# Adafruit_DragonTail.net
KiCad netlist of a schematic drawn in EAGLE
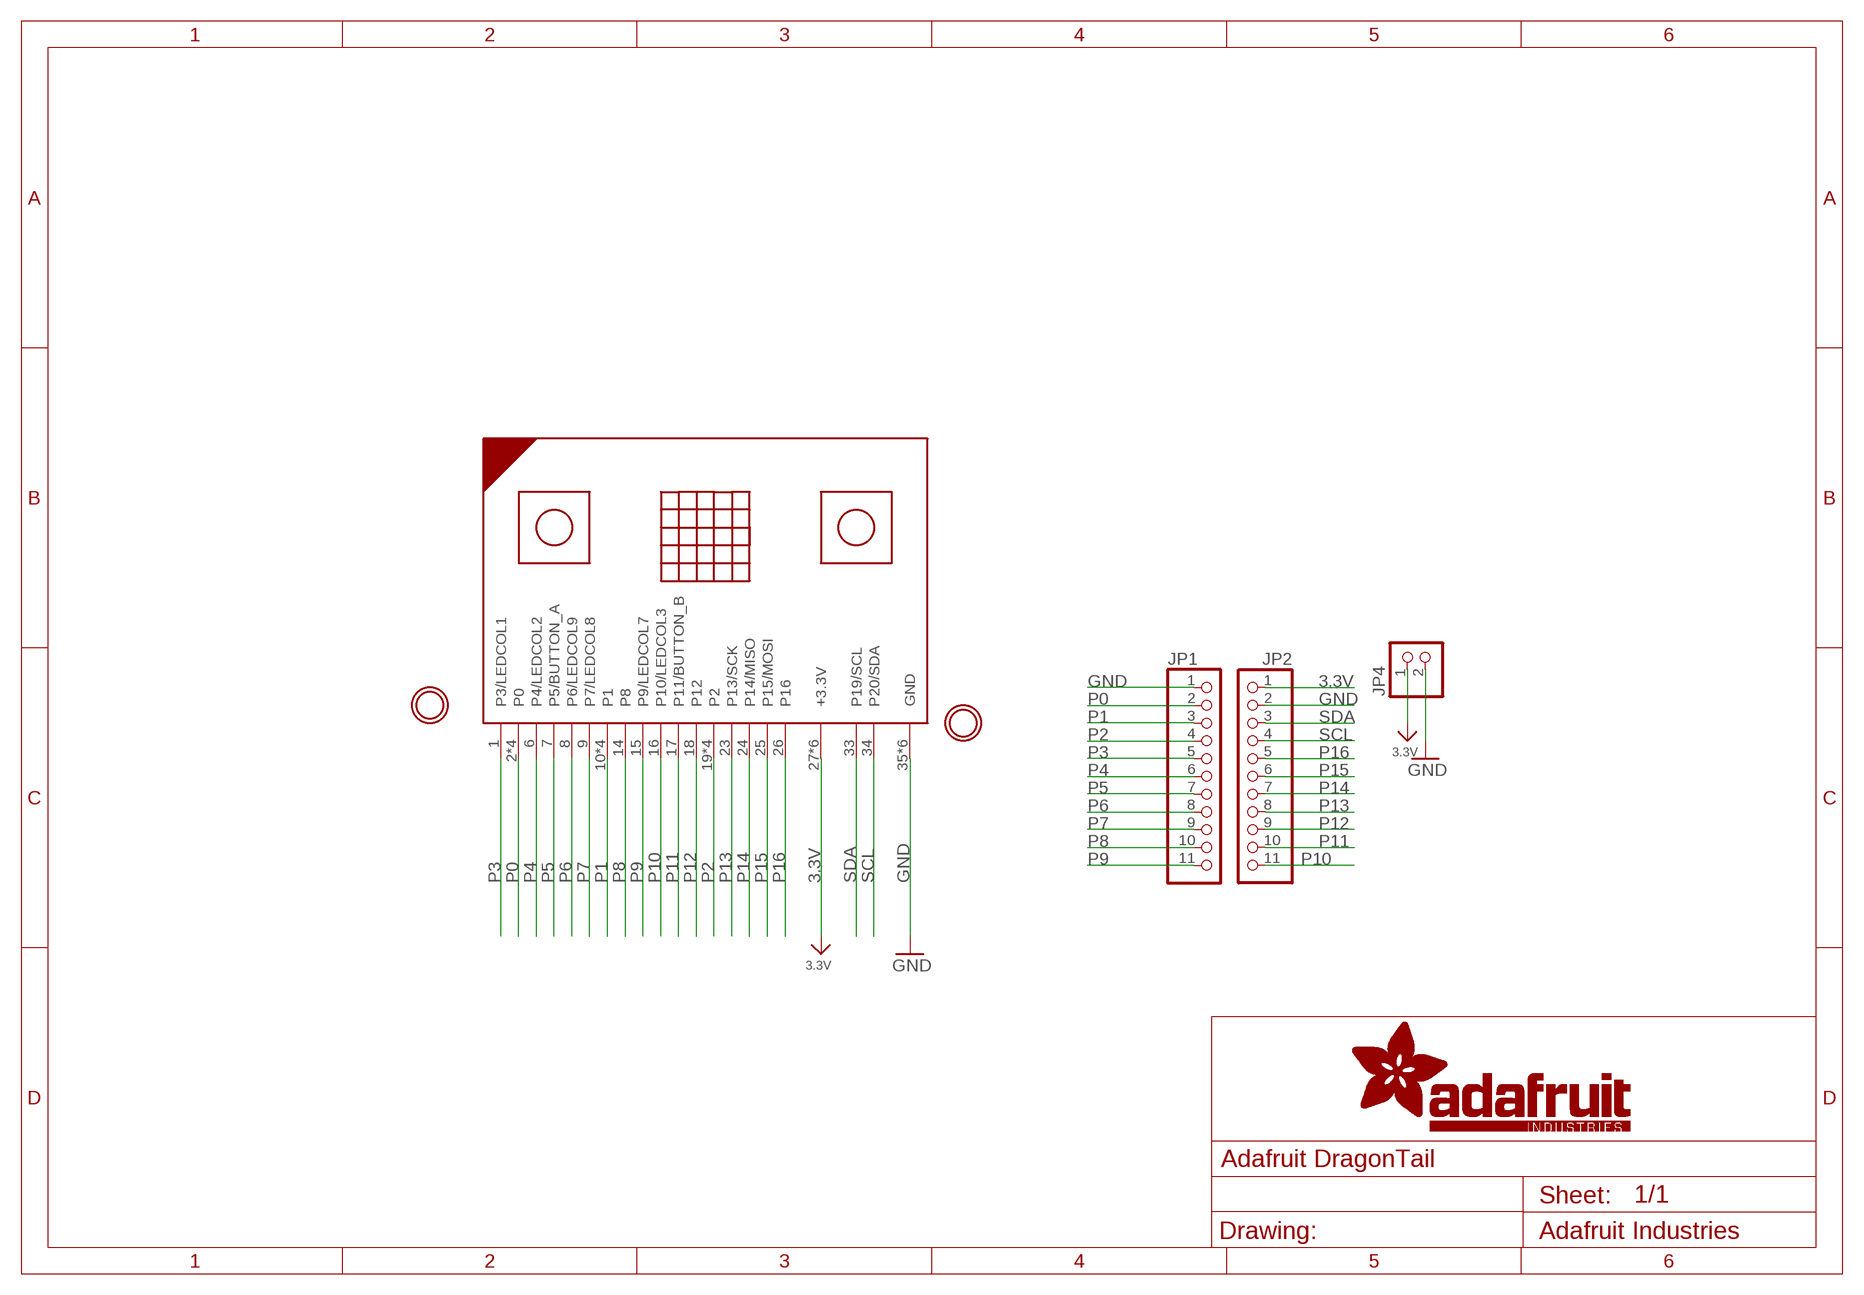
[diagram p0: schematic, sheet 1]

(export (version "E")
  (design (tool "Eeschema 10.0.6"))
  (components
    (comp (ref "JP1")
      (value "HEADER-1X1176MIL")
      (footprint "eagle-import:1X11_ROUND_76")
      (libsource (lib "eagle-import") (part "HEADER-1X1176MIL"))
    )
    (comp (ref "JP2")
      (value "HEADER-1X1176MIL")
      (footprint "eagle-import:1X11_ROUND_76")
      (libsource (lib "eagle-import") (part "HEADER-1X1176MIL"))
    )
    (comp (ref "JP4")
      (value "HEADER-1X2")
      (footprint "eagle-import:1X02_OVAL")
      (libsource (lib "eagle-import") (part "HEADER-1X2"))
    )
    (comp (ref "MB1")
      (value "MICRO:BIT_RA")
      (footprint "eagle-import:2X20_CARDEDGE_RA")
      (libsource (lib "eagle-import") (part "MICRO{colon}BIT_RA"))
    )
    (comp (ref "U$9")
      (value "MOUNTINGHOLE2.0")
      (footprint "eagle-import:MOUNTINGHOLE_2.0_PLATED")
      (libsource (lib "eagle-import") (part "MOUNTINGHOLE2.0"))
    )
    (comp (ref "U$10")
      (value "MOUNTINGHOLE2.0")
      (footprint "eagle-import:MOUNTINGHOLE_2.0_PLATED")
      (libsource (lib "eagle-import") (part "MOUNTINGHOLE2.0"))
    )
  )
  (nets
    (net (code "1") (name "/P0") (class "Default")
      (node (ref "JP1") (pin "2") (pinfunction "2_2") (pintype "passive"))
      (node (ref "MB1") (pin "2") (pinfunction "P0_2") (pintype "bidirectional"))
      (node (ref "MB1") (pin "3") (pinfunction "P0_3") (pintype "bidirectional"))
      (node (ref "MB1") (pin "4") (pinfunction "P0_4") (pintype "bidirectional"))
      (node (ref "MB1") (pin "5") (pinfunction "P0_5") (pintype "bidirectional"))
    )
    (net (code "2") (name "/P1") (class "Default")
      (node (ref "JP1") (pin "3") (pinfunction "3_3") (pintype "passive"))
      (node (ref "MB1") (pin "10") (pinfunction "P1_10") (pintype "bidirectional"))
      (node (ref "MB1") (pin "11") (pinfunction "P1_11") (pintype "bidirectional"))
      (node (ref "MB1") (pin "12") (pinfunction "P1_12") (pintype "bidirectional"))
      (node (ref "MB1") (pin "13") (pinfunction "P1_13") (pintype "bidirectional"))
    )
    (net (code "3") (name "/P2") (class "Default")
      (node (ref "JP1") (pin "4") (pinfunction "4_4") (pintype "passive"))
      (node (ref "MB1") (pin "19") (pinfunction "P2_19") (pintype "bidirectional"))
      (node (ref "MB1") (pin "20") (pinfunction "P2_20") (pintype "bidirectional"))
      (node (ref "MB1") (pin "21") (pinfunction "P2_21") (pintype "bidirectional"))
      (node (ref "MB1") (pin "22") (pinfunction "P2_22") (pintype "bidirectional"))
    )
    (net (code "4") (name "/P3") (class "Default")
      (node (ref "JP1") (pin "5") (pinfunction "5_5") (pintype "passive"))
      (node (ref "MB1") (pin "1") (pinfunction "P3/LEDCOL1_1") (pintype "bidirectional"))
    )
    (net (code "5") (name "/P4") (class "Default")
      (node (ref "JP1") (pin "6") (pinfunction "6_6") (pintype "passive"))
      (node (ref "MB1") (pin "6") (pinfunction "P4/LEDCOL2_6") (pintype "bidirectional"))
    )
    (net (code "6") (name "/P5") (class "Default")
      (node (ref "JP1") (pin "7") (pinfunction "7_7") (pintype "passive"))
      (node (ref "MB1") (pin "7") (pinfunction "P5/BUTTON_A_7") (pintype "bidirectional"))
    )
    (net (code "7") (name "/P6") (class "Default")
      (node (ref "JP1") (pin "8") (pinfunction "8_8") (pintype "passive"))
      (node (ref "MB1") (pin "8") (pinfunction "P6/LEDCOL9_8") (pintype "bidirectional"))
    )
    (net (code "8") (name "/P7") (class "Default")
      (node (ref "JP1") (pin "9") (pinfunction "9_9") (pintype "passive"))
      (node (ref "MB1") (pin "9") (pinfunction "P7/LEDCOL8_9") (pintype "bidirectional"))
    )
    (net (code "9") (name "/P8") (class "Default")
      (node (ref "JP1") (pin "10") (pinfunction "10_10") (pintype "passive"))
      (node (ref "MB1") (pin "14") (pinfunction "P8_14") (pintype "bidirectional"))
    )
    (net (code "10") (name "/P9") (class "Default")
      (node (ref "JP1") (pin "11") (pinfunction "11_11") (pintype "passive"))
      (node (ref "MB1") (pin "15") (pinfunction "P9/LEDCOL7_15") (pintype "bidirectional"))
    )
    (net (code "11") (name "/P10") (class "Default")
      (node (ref "JP2") (pin "11") (pinfunction "11_11") (pintype "passive"))
      (node (ref "MB1") (pin "16") (pinfunction "P10/LEDCOL3_16") (pintype "bidirectional"))
    )
    (net (code "12") (name "/P11") (class "Default")
      (node (ref "JP2") (pin "10") (pinfunction "10_10") (pintype "passive"))
      (node (ref "MB1") (pin "17") (pinfunction "P11/BUTTON_B_17") (pintype "bidirectional"))
    )
    (net (code "13") (name "/P12") (class "Default")
      (node (ref "JP2") (pin "9") (pinfunction "9_9") (pintype "passive"))
      (node (ref "MB1") (pin "18") (pinfunction "P12_18") (pintype "bidirectional"))
    )
    (net (code "14") (name "/P13") (class "Default")
      (node (ref "JP2") (pin "8") (pinfunction "8_8") (pintype "passive"))
      (node (ref "MB1") (pin "23") (pinfunction "P13/SCK_23") (pintype "bidirectional"))
    )
    (net (code "15") (name "/P14") (class "Default")
      (node (ref "JP2") (pin "7") (pinfunction "7_7") (pintype "passive"))
      (node (ref "MB1") (pin "24") (pinfunction "P14/MISO_24") (pintype "bidirectional"))
    )
    (net (code "16") (name "/P15") (class "Default")
      (node (ref "JP2") (pin "6") (pinfunction "6_6") (pintype "passive"))
      (node (ref "MB1") (pin "25") (pinfunction "P15/MOSI_25") (pintype "bidirectional"))
    )
    (net (code "17") (name "/P16") (class "Default")
      (node (ref "JP2") (pin "5") (pinfunction "5_5") (pintype "passive"))
      (node (ref "MB1") (pin "26") (pinfunction "P16_26") (pintype "bidirectional"))
    )
    (net (code "18") (name "/SCL") (class "Default")
      (node (ref "JP2") (pin "4") (pinfunction "4_4") (pintype "passive"))
      (node (ref "MB1") (pin "33") (pinfunction "P19/SCL_33") (pintype "bidirectional"))
    )
    (net (code "19") (name "/SDA") (class "Default")
      (node (ref "JP2") (pin "3") (pinfunction "3_3") (pintype "passive"))
      (node (ref "MB1") (pin "34") (pinfunction "P20/SDA_34") (pintype "bidirectional"))
    )
    (net (code "20") (name "3.3V") (class "Default")
      (node (ref "JP2") (pin "1") (pinfunction "1_1") (pintype "passive"))
      (node (ref "JP4") (pin "1") (pinfunction "1_1") (pintype "passive"))
      (node (ref "MB1") (pin "27") (pinfunction "+3.3V_27") (pintype "power_in"))
      (node (ref "MB1") (pin "28") (pinfunction "+3.3V_28") (pintype "power_in"))
      (node (ref "MB1") (pin "29") (pinfunction "+3.3V_29") (pintype "power_in"))
      (node (ref "MB1") (pin "30") (pinfunction "+3.3V_30") (pintype "power_in"))
      (node (ref "MB1") (pin "31") (pinfunction "+3.3V_31") (pintype "power_in"))
      (node (ref "MB1") (pin "32") (pinfunction "+3.3V_32") (pintype "power_in"))
    )
    (net (code "21") (name "GND") (class "Default")
      (node (ref "JP1") (pin "1") (pinfunction "1_1") (pintype "passive"))
      (node (ref "JP2") (pin "2") (pinfunction "2_2") (pintype "passive"))
      (node (ref "JP4") (pin "2") (pinfunction "2_2") (pintype "passive"))
      (node (ref "MB1") (pin "35") (pinfunction "GND_35") (pintype "power_in"))
      (node (ref "MB1") (pin "36") (pinfunction "GND_36") (pintype "power_in"))
      (node (ref "MB1") (pin "37") (pinfunction "GND_37") (pintype "power_in"))
      (node (ref "MB1") (pin "38") (pinfunction "GND_38") (pintype "power_in"))
      (node (ref "MB1") (pin "39") (pinfunction "GND_39") (pintype "power_in"))
      (node (ref "MB1") (pin "40") (pinfunction "GND_40") (pintype "power_in"))
    )
  )
)
